# Network.net
KiCad netlist of a schematic drawn in Altium Designer
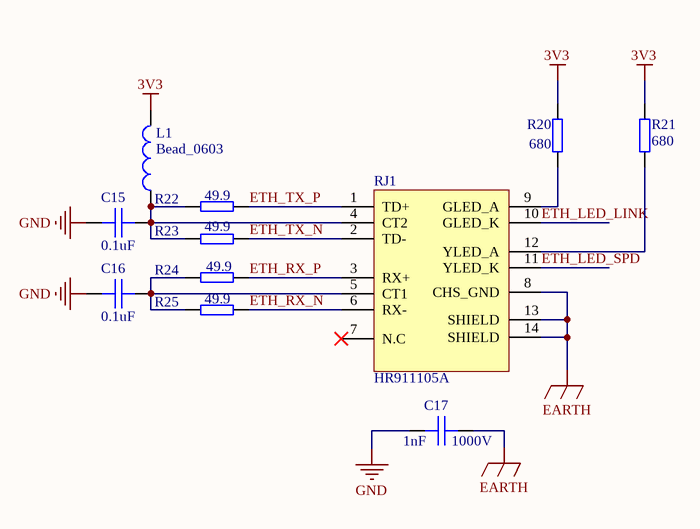
[diagram p0: Network.SchDoc]

(export (version "E")
  (design (tool "Eeschema 10.0.6"))
  (components
    (comp (ref "C15")
      (value "0.1uF")
      (footprint "CAP-0603")
      (description "陶瓷贴片电容0603")
      (fields (field (name "TOLERANCE") "10%") (field (name "VOLTAGE") "50V"))
      (libsource (lib "momo") (part "C_0603"))
    )
    (comp (ref "C16")
      (value "0.1uF")
      (footprint "CAP-0603")
      (description "陶瓷贴片电容0603")
      (fields (field (name "TOLERANCE") "10%") (field (name "VOLTAGE") "50V"))
      (libsource (lib "momo") (part "C_0603"))
    )
    (comp (ref "C17")
      (value "1nF")
      (footprint "CAP-1206")
      (description "陶瓷贴片电容1206")
      (fields (field (name "TOLERANCE") "10%") (field (name "VOLTAGE") "1000V"))
      (libsource (lib "momo") (part "C_1206"))
    )
    (comp (ref "L1")
      (value "Bead_0603")
      (footprint "L-0603")
      (description "贴片磁珠0603")
      (libsource (lib "momo") (part "Bead_0603"))
    )
    (comp (ref "R20")
      (value "680")
      (footprint "RES-0603")
      (description "贴片电阻0603")
      (fields (field (name "TOLERANCE") "5%") (field (name "VOLTAGE") "50V"))
      (libsource (lib "momo") (part "R_0603"))
    )
    (comp (ref "R21")
      (value "680")
      (footprint "RES-0603")
      (description "贴片电阻0603")
      (fields (field (name "TOLERANCE") "5%") (field (name "VOLTAGE") "50V"))
      (libsource (lib "momo") (part "R_0603"))
    )
    (comp (ref "R22")
      (value "49.9")
      (footprint "RES-0603")
      (description "贴片电阻0603")
      (fields (field (name "TOLERANCE") "5%") (field (name "VOLTAGE") "50V"))
      (libsource (lib "momo") (part "R_0603"))
    )
    (comp (ref "R23")
      (value "49.9")
      (footprint "RES-0603")
      (description "贴片电阻0603")
      (fields (field (name "TOLERANCE") "5%") (field (name "VOLTAGE") "50V"))
      (libsource (lib "momo") (part "R_0603"))
    )
    (comp (ref "R24")
      (value "49.9")
      (footprint "RES-0603")
      (description "贴片电阻0603")
      (fields (field (name "TOLERANCE") "5%") (field (name "VOLTAGE") "50V"))
      (libsource (lib "momo") (part "R_0603"))
    )
    (comp (ref "R25")
      (value "49.9")
      (footprint "RES-0603")
      (description "贴片电阻0603")
      (fields (field (name "TOLERANCE") "5%") (field (name "VOLTAGE") "50V"))
      (libsource (lib "momo") (part "R_0603"))
    )
    (comp (ref "RJ1")
      (value "HR911105A")
      (footprint "momo:HR911105A")
      (description "Header, 8-Pin, Dual row")
      (fields (field (name "PUBLISHER") "Altium Limited"))
      (libsource (lib "momo") (part "HR911105A"))
    )
  )
  (nets
    (net (code "1") (name "/ETH_LED_LINK") (class "Default")
      (node (ref "RJ1") (pin "10") (pinfunction "GLED_K_10") (pintype "passive"))
    )
    (net (code "2") (name "/ETH_LED_SPD") (class "Default")
      (node (ref "RJ1") (pin "11") (pinfunction "YLED_K_11") (pintype "passive"))
    )
    (net (code "3") (name "/ETH_RX_N") (class "Default")
      (node (ref "R25") (pin "1") (pinfunction "1_1") (pintype "passive"))
      (node (ref "RJ1") (pin "6") (pinfunction "RX-_6") (pintype "passive"))
    )
    (net (code "4") (name "/ETH_RX_P") (class "Default")
      (node (ref "R24") (pin "1") (pinfunction "1_1") (pintype "passive"))
      (node (ref "RJ1") (pin "3") (pinfunction "RX+_3") (pintype "passive"))
    )
    (net (code "5") (name "/ETH_TX_N") (class "Default")
      (node (ref "R23") (pin "1") (pinfunction "1_1") (pintype "passive"))
      (node (ref "RJ1") (pin "2") (pinfunction "TD-_2") (pintype "passive"))
    )
    (net (code "6") (name "/ETH_TX_P") (class "Default")
      (node (ref "R22") (pin "1") (pinfunction "1_1") (pintype "passive"))
      (node (ref "RJ1") (pin "1") (pinfunction "TD+_1") (pintype "passive"))
    )
    (net (code "7") (name "3V3") (class "Default")
      (node (ref "L1") (pin "2") (pinfunction "2_2") (pintype "passive"))
      (node (ref "R20") (pin "2") (pinfunction "2_2") (pintype "passive"))
      (node (ref "R21") (pin "1") (pinfunction "1_1") (pintype "passive"))
    )
    (net (code "8") (name "EARTH") (class "Default")
      (node (ref "C17") (pin "2") (pinfunction "2_2") (pintype "passive"))
      (node (ref "RJ1") (pin "13") (pinfunction "SHIELD_13") (pintype "power_in"))
      (node (ref "RJ1") (pin "14") (pinfunction "SHIELD_14") (pintype "power_in"))
      (node (ref "RJ1") (pin "8") (pinfunction "CHS_GND_8") (pintype "passive"))
    )
    (net (code "9") (name "GND") (class "Default")
      (node (ref "C15") (pin "1") (pinfunction "1_1") (pintype "passive"))
      (node (ref "C16") (pin "1") (pinfunction "1_1") (pintype "passive"))
      (node (ref "C17") (pin "1") (pinfunction "1_1") (pintype "passive"))
    )
    (net (code "10") (name "Net-(RJ1-CT1)") (class "Default")
      (node (ref "C16") (pin "2") (pinfunction "2_2") (pintype "passive"))
      (node (ref "R24") (pin "2") (pinfunction "2_2") (pintype "passive"))
      (node (ref "R25") (pin "2") (pinfunction "2_2") (pintype "passive"))
      (node (ref "RJ1") (pin "5") (pinfunction "CT1_5") (pintype "passive"))
    )
    (net (code "11") (name "Net-(RJ1-CT2)") (class "Default")
      (node (ref "C15") (pin "2") (pinfunction "2_2") (pintype "passive"))
      (node (ref "L1") (pin "1") (pinfunction "1_1") (pintype "passive"))
      (node (ref "R22") (pin "2") (pinfunction "2_2") (pintype "passive"))
      (node (ref "R23") (pin "2") (pinfunction "2_2") (pintype "passive"))
      (node (ref "RJ1") (pin "4") (pinfunction "CT2_4") (pintype "passive"))
    )
    (net (code "12") (name "Net-(RJ1-GLED_A)") (class "Default")
      (node (ref "R20") (pin "1") (pinfunction "1_1") (pintype "passive"))
      (node (ref "RJ1") (pin "9") (pinfunction "GLED_A_9") (pintype "passive"))
    )
    (net (code "13") (name "Net-(RJ1-YLED_A)") (class "Default")
      (node (ref "R21") (pin "2") (pinfunction "2_2") (pintype "passive"))
      (node (ref "RJ1") (pin "12") (pinfunction "YLED_A_12") (pintype "passive"))
    )
    (net (code "14") (name "unconnected-(RJ1-N.C-Pad7)") (class "Default")
      (node (ref "RJ1") (pin "7") (pinfunction "N.C_7") (pintype "passive+no_connect"))
    )
  )
)
